# GNSS.net
KiCad netlist of a schematic drawn in Altium Designer
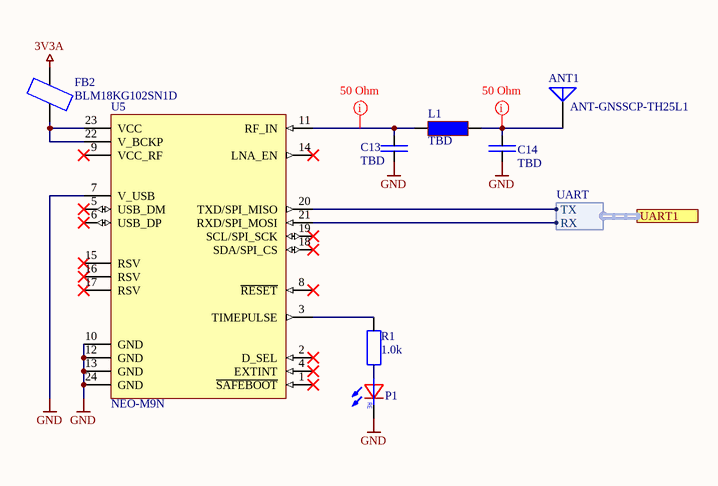
[diagram p0: GNSS.SchDoc]

(export (version "E")
  (design (tool "Eeschema 10.0.6"))
  (components
    (comp (ref "ANT1")
      (value "ANT-GNSSCP-TH25L1")
      (footprint "THT Antenna ANT-GNSSCP-TH25L1")
      (libsource (lib "RF") (part "ANT-GNSSCP-TH25L1"))
    )
    (comp (ref "C13")
      (value "TBD")
      (footprint "SMD Keramikkondensator 0402")
      (description "SMD Ceramic Capacitor E6")
      (libsource (lib "Ceramic Capacitors-E6") (part "E6 - 10pF"))
    )
    (comp (ref "C14")
      (value "TBD")
      (footprint "SMD Keramikkondensator 0402")
      (description "SMD Ceramic Capacitor E6")
      (libsource (lib "Ceramic Capacitors-E6") (part "E6 - 10pF"))
    )
    (comp (ref "FB2")
      (value "BLM18KG102SN1D")
      (footprint "SMD Ferrite Bead 0603")
      (description "1 kOhms @ 100MHz 1 Power Line Ferrite Bead 0603 (1608 Metric) 1A 200mOhm")
      (libsource (lib "Inductors") (part "BLM18KG102SN1D"))
    )
    (comp (ref "L1")
      (value "TBD")
      (footprint "SMD Ferrite Bead 0402")
      (description "Pi-Matchng Inductor")
      (libsource (lib "Inductors") (part "Inductor Pi-Matching"))
    )
    (comp (ref "P1")
      (value "LED")
      (footprint "SMD LED 0603")
      (description "Color LED")
      (libsource (lib "Diodes") (part "LED"))
    )
    (comp (ref "R1")
      (value "1.0k")
      (footprint "SMD Widerstand 0603")
      (description "SMD Chip Resistor E24")
      (libsource (lib "Resistors-E24") (part "E24 - 1.0k"))
    )
    (comp (ref "U5")
      (value "NEO-M9N")
      (footprint "SMD NEO")
      (description "u-blox M9 standard precision module")
      (libsource (lib "Sensors") (part "NEO-M9N"))
    )
  )
  (nets
    (net (code "2") (name "/RX") (class "Default")
      (node (ref "U5") (pin "21") (pinfunction "RXD/SPI_MOSI_21") (pintype "input"))
    )
    (net (code "3") (name "/TX") (class "Default")
      (node (ref "U5") (pin "20") (pinfunction "TXD/SPI_MISO_20") (pintype "output"))
    )
    (net (code "5") (name "3V3A") (class "Default")
      (node (ref "FB2") (pin "2") (pinfunction "2_2") (pintype "passive"))
    )
    (net (code "6") (name "GND") (class "Default")
      (node (ref "C13") (pin "1") (pinfunction "1_1") (pintype "passive"))
      (node (ref "C14") (pin "1") (pinfunction "1_1") (pintype "passive"))
      (node (ref "P1") (pin "K") (pinfunction "K_K") (pintype "passive"))
      (node (ref "U5") (pin "10") (pinfunction "GND_10") (pintype "passive"))
      (node (ref "U5") (pin "12") (pinfunction "GND_12") (pintype "passive"))
      (node (ref "U5") (pin "13") (pinfunction "GND_13") (pintype "passive"))
      (node (ref "U5") (pin "24") (pinfunction "GND_24") (pintype "passive"))
      (node (ref "U5") (pin "7") (pinfunction "V_USB_7") (pintype "passive"))
    )
    (net (code "7") (name "Net-(ANT1-Pad1)") (class "Default")
      (node (ref "ANT1") (pin "1") (pinfunction "1_1") (pintype "passive"))
      (node (ref "C14") (pin "2") (pinfunction "2_2") (pintype "passive"))
      (node (ref "L1") (pin "2") (pinfunction "2_2") (pintype "passive"))
    )
    (net (code "8") (name "Net-(P1-PadA)") (class "Default")
      (node (ref "P1") (pin "A") (pinfunction "A_A") (pintype "passive"))
      (node (ref "R1") (pin "1") (pinfunction "1_1") (pintype "passive"))
    )
    (net (code "9") (name "Net-(U5-RF_IN)") (class "Default")
      (node (ref "C13") (pin "2") (pinfunction "2_2") (pintype "passive"))
      (node (ref "L1") (pin "1") (pinfunction "1_1") (pintype "passive"))
      (node (ref "U5") (pin "11") (pinfunction "RF_IN_11") (pintype "input"))
    )
    (net (code "10") (name "Net-(U5-TIMEPULSE)") (class "Default")
      (node (ref "R1") (pin "2") (pinfunction "2_2") (pintype "passive"))
      (node (ref "U5") (pin "3") (pinfunction "TIMEPULSE_3") (pintype "output"))
    )
    (net (code "11") (name "Net-(U5-VCC)") (class "Default")
      (node (ref "FB2") (pin "1") (pinfunction "1_1") (pintype "passive"))
      (node (ref "U5") (pin "22") (pinfunction "V_BCKP_22") (pintype "passive"))
      (node (ref "U5") (pin "23") (pinfunction "VCC_23") (pintype "passive"))
    )
    (net (code "12") (name "unconnected-(U5-D_SEL-Pad2)") (class "Default")
      (node (ref "U5") (pin "2") (pinfunction "D_SEL_2") (pintype "input+no_connect"))
    )
    (net (code "13") (name "unconnected-(U5-EXTINT-Pad4)") (class "Default")
      (node (ref "U5") (pin "4") (pinfunction "EXTINT_4") (pintype "input+no_connect"))
    )
    (net (code "14") (name "unconnected-(U5-LNA_EN-Pad14)") (class "Default")
      (node (ref "U5") (pin "14") (pinfunction "LNA_EN_14") (pintype "output+no_connect"))
    )
    (net (code "15") (name "unconnected-(U5-RSV-Pad15)") (class "Default")
      (node (ref "U5") (pin "15") (pinfunction "RSV_15") (pintype "passive+no_connect"))
    )
    (net (code "16") (name "unconnected-(U5-RSV-Pad16)") (class "Default")
      (node (ref "U5") (pin "16") (pinfunction "RSV_16") (pintype "passive+no_connect"))
    )
    (net (code "17") (name "unconnected-(U5-RSV-Pad17)") (class "Default")
      (node (ref "U5") (pin "17") (pinfunction "RSV_17") (pintype "passive+no_connect"))
    )
    (net (code "18") (name "unconnected-(U5-SCL{slash}SPI_SCK-Pad19)") (class "Default")
      (node (ref "U5") (pin "19") (pinfunction "SCL/SPI_SCK_19") (pintype "bidirectional+no_connect"))
    )
    (net (code "19") (name "unconnected-(U5-SDA{slash}SPI_CS-Pad18)") (class "Default")
      (node (ref "U5") (pin "18") (pinfunction "SDA/SPI_CS_18") (pintype "bidirectional+no_connect"))
    )
    (net (code "20") (name "unconnected-(U5-USB_DM-Pad5)") (class "Default")
      (node (ref "U5") (pin "5") (pinfunction "USB_DM_5") (pintype "bidirectional+no_connect"))
    )
    (net (code "21") (name "unconnected-(U5-USB_DP-Pad6)") (class "Default")
      (node (ref "U5") (pin "6") (pinfunction "USB_DP_6") (pintype "bidirectional+no_connect"))
    )
    (net (code "22") (name "unconnected-(U5-VCC_RF-Pad9)") (class "Default")
      (node (ref "U5") (pin "9") (pinfunction "VCC_RF_9") (pintype "passive+no_connect"))
    )
    (net (code "23") (name "unconnected-(U5-~{RESET}-Pad8)") (class "Default")
      (node (ref "U5") (pin "8") (pinfunction "~{RESET}_8") (pintype "input+no_connect"))
    )
    (net (code "24") (name "unconnected-(U5-~{SAFEBOOT}-Pad1)") (class "Default")
      (node (ref "U5") (pin "1") (pinfunction "~{SAFEBOOT}_1") (pintype "input+no_connect"))
    )
  )
)
